# Discharge.net
KiCad netlist of a schematic drawn in Altium Designer
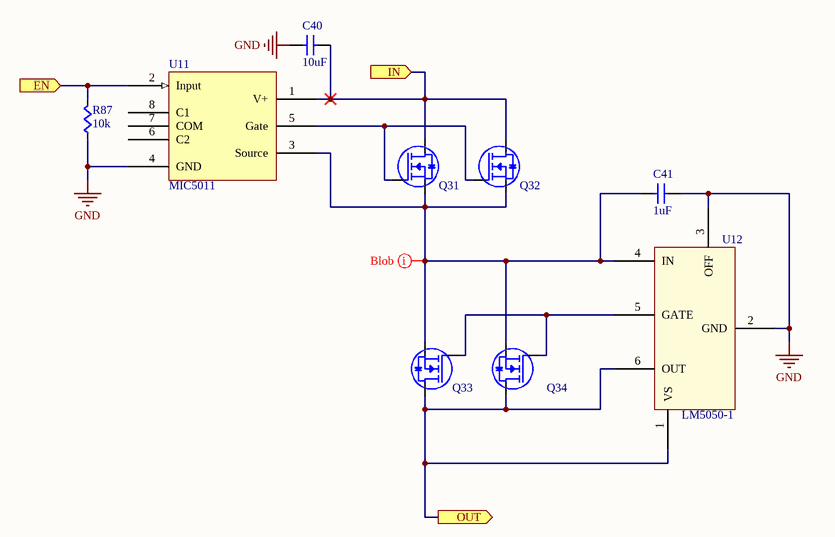
[diagram p0: Discharge.SchDoc]

(export (version "E")
  (design (tool "Eeschema 10.0.6"))
  (components
    (comp (ref "C40")
      (value "10uF")
      (footprint "CAPC1206")
      (fields (field (name "Comment") "Cap"))
      (libsource (lib "SubjuGator8") (part "Cap"))
    )
    (comp (ref "C41")
      (value "1uF")
      (footprint "CAPC0805")
      (fields (field (name "Comment") "Cap"))
      (libsource (lib "SubjuGator8") (part "Cap"))
    )
    (comp (ref "Q31")
      (value "IRFB3306PbF")
      (footprint "TO-220AB Heatsink")
      (description "HEXFET Power MOSFET")
      (libsource (lib "") (part "IRFx3306PbF_1"))
    )
    (comp (ref "Q32")
      (value "IRFB3306PbF")
      (footprint "TO-220AB Heatsink")
      (description "HEXFET Power MOSFET")
      (libsource (lib "") (part "IRFx3306PbF_1"))
    )
    (comp (ref "Q33")
      (value "IRFB3306PbF")
      (footprint "TO-220AB Heatsink")
      (description "HEXFET Power MOSFET")
      (libsource (lib "SubjuGator8") (part "IRFx3306PbF"))
    )
    (comp (ref "Q34")
      (value "IRFB3306PbF")
      (footprint "TO-220AB Heatsink")
      (description "HEXFET Power MOSFET")
      (libsource (lib "SubjuGator8") (part "IRFx3306PbF"))
    )
    (comp (ref "R87")
      (value "10k")
      (footprint "RES0603")
      (fields (field (name "Comment") "Res"))
      (libsource (lib "SubjuGator8") (part "Res"))
    )
    (comp (ref "U11")
      (value "MIC5011")
      (footprint "MIC5011")
      (description "Minimum Parts High- or Low-Side MOSFET Driver")
      (libsource (lib "SubjuGator8") (part "MIC5011"))
    )
    (comp (ref "U12")
      (value "LM5050-1")
      (footprint "LM5050")
      (description "High-Side OR-ing FET Controller")
      (libsource (lib "SubjuGator8") (part "LM5050"))
    )
  )
  (nets
    (net (code "1") (name "/EN") (class "Default")
      (node (ref "R87") (pin "1") (pinfunction "A_1") (pintype "passive"))
      (node (ref "U11") (pin "2") (pinfunction "Input_2") (pintype "input"))
    )
    (net (code "2") (name "/IN") (class "Default")
      (node (ref "C40") (pin "2") (pinfunction "B_2") (pintype "passive"))
      (node (ref "Q31") (pin "D") (pinfunction "D_D") (pintype "passive"))
      (node (ref "Q32") (pin "D") (pinfunction "D_D") (pintype "passive"))
      (node (ref "U11") (pin "1") (pinfunction "V+_1") (pintype "power_in"))
    )
    (net (code "3") (name "/OUT") (class "Default")
      (node (ref "Q33") (pin "D") (pinfunction "D_D") (pintype "passive"))
      (node (ref "Q34") (pin "D") (pinfunction "D_D") (pintype "passive"))
      (node (ref "U12") (pin "1") (pinfunction "VS_1") (pintype "passive"))
      (node (ref "U12") (pin "6") (pinfunction "OUT_6") (pintype "passive"))
    )
    (net (code "4") (name "GND") (class "Default")
      (node (ref "C40") (pin "1") (pinfunction "A_1") (pintype "passive"))
      (node (ref "C41") (pin "1") (pinfunction "A_1") (pintype "passive"))
      (node (ref "R87") (pin "2") (pinfunction "B_2") (pintype "passive"))
      (node (ref "U11") (pin "4") (pinfunction "GND_4") (pintype "power_in"))
      (node (ref "U12") (pin "2") (pinfunction "GND_2") (pintype "passive"))
      (node (ref "U12") (pin "3") (pinfunction "OFF_3") (pintype "passive"))
    )
    (net (code "5") (name "Net-(C41-B)") (class "Default")
      (node (ref "C41") (pin "2") (pinfunction "B_2") (pintype "passive"))
      (node (ref "Q31") (pin "S") (pinfunction "S_S") (pintype "passive"))
      (node (ref "Q32") (pin "S") (pinfunction "S_S") (pintype "passive"))
      (node (ref "Q33") (pin "S") (pinfunction "S_S") (pintype "passive"))
      (node (ref "Q34") (pin "S") (pinfunction "S_S") (pintype "passive"))
      (node (ref "U11") (pin "3") (pinfunction "Source_3") (pintype "passive"))
      (node (ref "U12") (pin "4") (pinfunction "IN_4") (pintype "passive"))
    )
    (net (code "6") (name "Net-(U11-Gate)") (class "Default")
      (node (ref "Q31") (pin "G") (pinfunction "G_G") (pintype "passive"))
      (node (ref "Q32") (pin "G") (pinfunction "G_G") (pintype "passive"))
      (node (ref "U11") (pin "5") (pinfunction "Gate_5") (pintype "passive"))
    )
    (net (code "7") (name "Net-(U12-GATE)") (class "Default")
      (node (ref "Q33") (pin "G") (pinfunction "G_G") (pintype "passive"))
      (node (ref "Q34") (pin "G") (pinfunction "G_G") (pintype "passive"))
      (node (ref "U12") (pin "5") (pinfunction "GATE_5") (pintype "passive"))
    )
    (net (code "8") (name "unconnected-(U11-C1-Pad8)") (class "Default")
      (node (ref "U11") (pin "8") (pinfunction "C1_8") (pintype "passive"))
    )
    (net (code "9") (name "unconnected-(U11-C2-Pad6)") (class "Default")
      (node (ref "U11") (pin "6") (pinfunction "C2_6") (pintype "passive"))
    )
    (net (code "10") (name "unconnected-(U11-COM-Pad7)") (class "Default")
      (node (ref "U11") (pin "7") (pinfunction "COM_7") (pintype "passive"))
    )
  )
)
